# UFl_calKit.net
KiCad netlist of a schematic drawn in Altium Designer
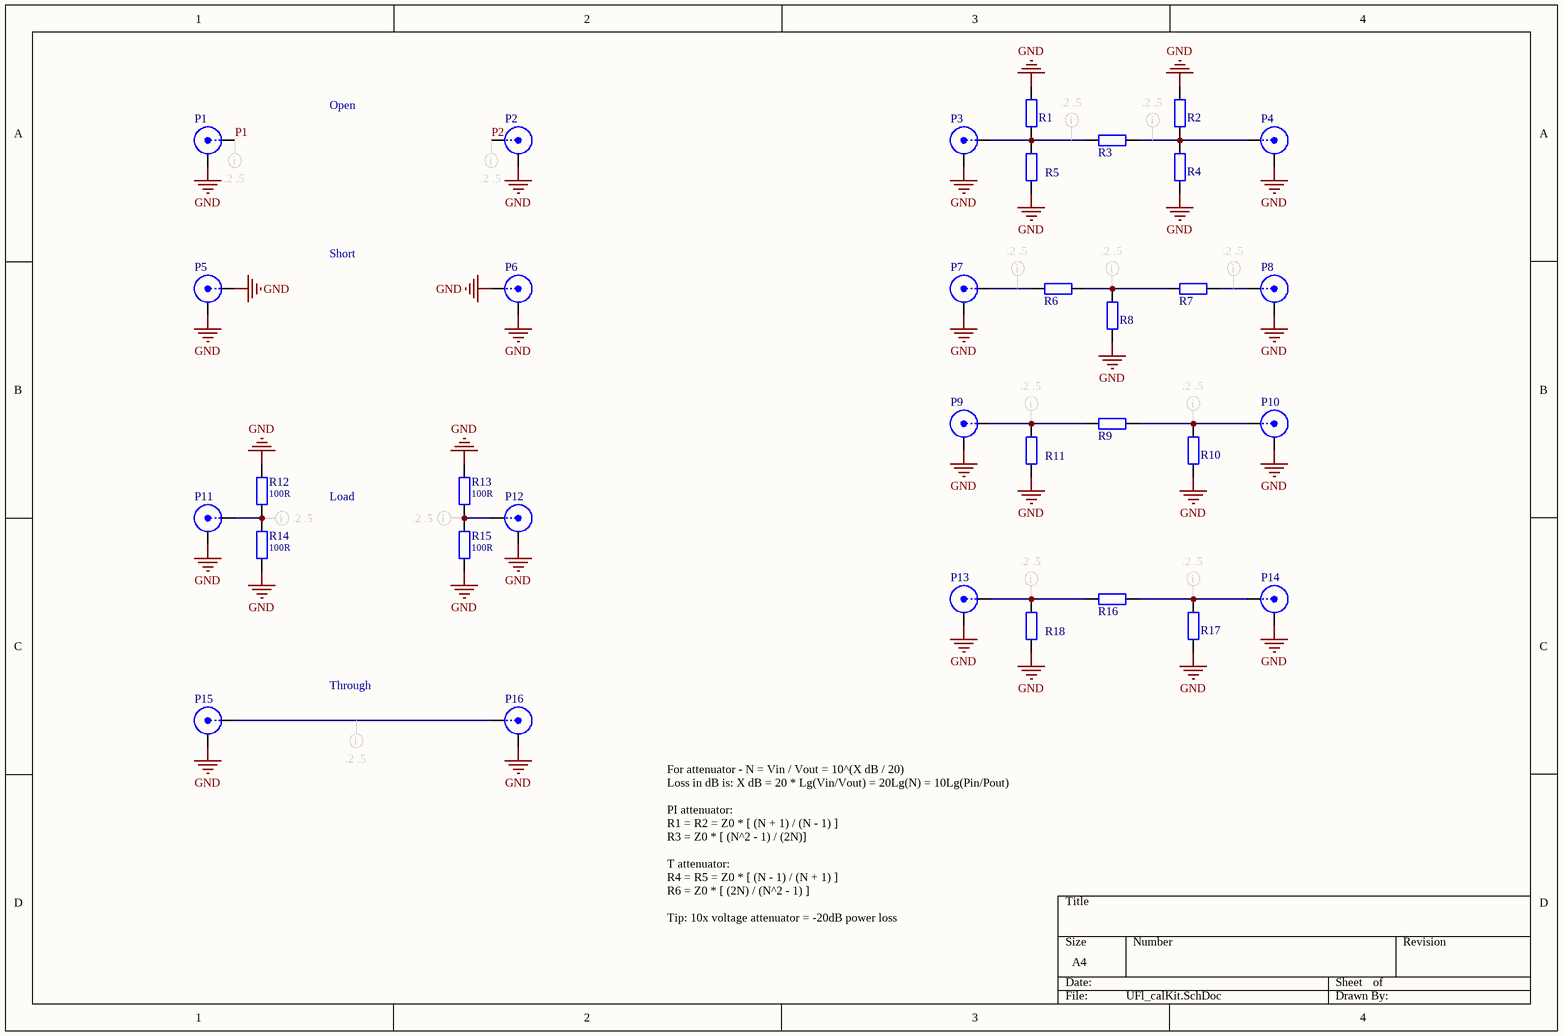
[diagram p0: UFl_calKit.SchDoc]

(export (version "E")
  (design (tool "Eeschema 10.0.6"))
  (components
    (comp (ref "P1")
      (value "U.Fl.")
      (footprint "U.FL CalKit")
      (libsource (lib "Miscellaneous Connectors") (part "BNC"))
    )
    (comp (ref "P2")
      (value "U.Fl.")
      (footprint "U.FL CalKit")
      (libsource (lib "Miscellaneous Connectors") (part "BNC"))
    )
    (comp (ref "P3")
      (value "U.Fl.")
      (footprint "U.FL CalKit")
      (libsource (lib "Miscellaneous Connectors") (part "BNC"))
    )
    (comp (ref "P4")
      (value "U.Fl.")
      (footprint "U.FL CalKit")
      (libsource (lib "Miscellaneous Connectors") (part "BNC"))
    )
    (comp (ref "P5")
      (value "U.Fl.")
      (footprint "U.FL-R-SMT-1(10)")
      (libsource (lib "Miscellaneous Connectors") (part "BNC"))
    )
    (comp (ref "P6")
      (value "U.Fl.")
      (footprint "U.FL-R-SMT-1(10)")
      (libsource (lib "Miscellaneous Connectors") (part "BNC"))
    )
    (comp (ref "P7")
      (value "U.Fl.")
      (footprint "U.FL CalKit")
      (libsource (lib "Miscellaneous Connectors") (part "BNC"))
    )
    (comp (ref "P8")
      (value "U.Fl.")
      (footprint "U.FL CalKit")
      (libsource (lib "Miscellaneous Connectors") (part "BNC"))
    )
    (comp (ref "P9")
      (value "U.Fl.")
      (footprint "U.FL CalKit")
      (libsource (lib "Miscellaneous Connectors") (part "BNC"))
    )
    (comp (ref "P10")
      (value "U.Fl.")
      (footprint "U.FL CalKit")
      (libsource (lib "Miscellaneous Connectors") (part "BNC"))
    )
    (comp (ref "P11")
      (value "U.Fl.")
      (footprint "U.FL CalKit")
      (libsource (lib "Miscellaneous Connectors") (part "BNC"))
    )
    (comp (ref "P12")
      (value "U.Fl.")
      (footprint "U.FL CalKit")
      (libsource (lib "Miscellaneous Connectors") (part "BNC"))
    )
    (comp (ref "P13")
      (value "U.Fl.")
      (footprint "U.FL CalKit")
      (libsource (lib "Miscellaneous Connectors") (part "BNC"))
    )
    (comp (ref "P14")
      (value "U.Fl.")
      (footprint "U.FL CalKit")
      (libsource (lib "Miscellaneous Connectors") (part "BNC"))
    )
    (comp (ref "P15")
      (value "U.Fl.")
      (footprint "U.FL CalKit")
      (libsource (lib "Miscellaneous Connectors") (part "BNC"))
    )
    (comp (ref "P16")
      (value "U.Fl.")
      (footprint "U.FL CalKit")
      (libsource (lib "Miscellaneous Connectors") (part "BNC"))
    )
    (comp (ref "R1")
      (value "0R, 50 V, 0402, 62.5 mW, ± 1%")
      (footprint "C SMD ceramic 0402 RF with silkscreen")
      (fields (field (name "PART NUMBER") "0402WGJ0000TCE") (field (name "MANUFACTURER") "ROYAL OHM"))
      (libsource (lib "Resistors") (part "Resistor"))
    )
    (comp (ref "R2")
      (value "0R, 50 V, 0402, 62.5 mW, ± 1%")
      (footprint "C SMD ceramic 0402 RF with silkscreen")
      (fields (field (name "PART NUMBER") "0402WGJ0000TCE") (field (name "MANUFACTURER") "ROYAL OHM"))
      (libsource (lib "Resistors") (part "Resistor"))
    )
    (comp (ref "R3")
      (value "0R, 50 V, 0402, 62.5 mW, ± 1%")
      (footprint "C SMD ceramic 0402 RF with silkscreen")
      (fields (field (name "PART NUMBER") "0402WGJ0000TCE") (field (name "MANUFACTURER") "ROYAL OHM"))
      (libsource (lib "Resistors") (part "Resistor"))
    )
    (comp (ref "R4")
      (value "0R, 50 V, 0402, 62.5 mW, ± 1%")
      (footprint "C SMD ceramic 0402 RF with silkscreen")
      (fields (field (name "PART NUMBER") "0402WGJ0000TCE") (field (name "MANUFACTURER") "ROYAL OHM"))
      (libsource (lib "Resistors") (part "Resistor"))
    )
    (comp (ref "R5")
      (value "0R, 50 V, 0402, 62.5 mW, ± 1%")
      (footprint "C SMD ceramic 0402 RF with silkscreen")
      (fields (field (name "PART NUMBER") "0402WGJ0000TCE") (field (name "MANUFACTURER") "ROYAL OHM"))
      (libsource (lib "Resistors") (part "Resistor"))
    )
    (comp (ref "R6")
      (value "0R, 50 V, 0402, 62.5 mW, ± 1%")
      (footprint "WE Match B")
      (fields (field (name "PART NUMBER") "0402WGJ0000TCE") (field (name "MANUFACTURER") "ROYAL OHM"))
      (libsource (lib "Resistors") (part "Resistor"))
    )
    (comp (ref "R7")
      (value "0R, 50 V, 0402, 62.5 mW, ± 1%")
      (footprint "WE Match B")
      (fields (field (name "PART NUMBER") "0402WGJ0000TCE") (field (name "MANUFACTURER") "ROYAL OHM"))
      (libsource (lib "Resistors") (part "Resistor"))
    )
    (comp (ref "R8")
      (value "0R, 50 V, 0402, 62.5 mW, ± 1%")
      (footprint "WE Match B")
      (fields (field (name "PART NUMBER") "0402WGJ0000TCE") (field (name "MANUFACTURER") "ROYAL OHM"))
      (libsource (lib "Resistors") (part "Resistor"))
    )
    (comp (ref "R9")
      (value "0R, 50 V, 0402, 62.5 mW, ± 1%")
      (footprint "WE Match B")
      (fields (field (name "PART NUMBER") "0402WGJ0000TCE") (field (name "MANUFACTURER") "ROYAL OHM"))
      (libsource (lib "Resistors") (part "Resistor"))
    )
    (comp (ref "R10")
      (value "0R, 50 V, 0402, 62.5 mW, ± 1%")
      (footprint "WE Match B")
      (fields (field (name "PART NUMBER") "0402WGJ0000TCE") (field (name "MANUFACTURER") "ROYAL OHM"))
      (libsource (lib "Resistors") (part "Resistor"))
    )
    (comp (ref "R11")
      (value "0R, 50 V, 0402, 62.5 mW, ± 1%")
      (footprint "WE Match B")
      (fields (field (name "PART NUMBER") "0402WGJ0000TCE") (field (name "MANUFACTURER") "ROYAL OHM"))
      (libsource (lib "Resistors") (part "Resistor"))
    )
    (comp (ref "R12")
      (value "100R")
      (footprint "C SMD ceramic 0402 RF")
      (description "100R, 50 V, 0402, 62.5 mW, ± 1%")
      (fields (field (name "PART NUMBER") "AC0402FR-10100RL") (field (name "MANUFACTURER") "YAGEO"))
      (libsource (lib "Resistors") (part "Resistor"))
    )
    (comp (ref "R13")
      (value "100R")
      (footprint "C SMD ceramic 0402 RF")
      (description "100R, 50 V, 0402, 62.5 mW, ± 1%")
      (fields (field (name "PART NUMBER") "AC0402FR-10100RL") (field (name "MANUFACTURER") "YAGEO"))
      (libsource (lib "Resistors") (part "Resistor"))
    )
    (comp (ref "R14")
      (value "100R")
      (footprint "C SMD ceramic 0402 RF")
      (description "100R, 50 V, 0402, 62.5 mW, ± 1%")
      (fields (field (name "PART NUMBER") "AC0402FR-10100RL") (field (name "MANUFACTURER") "YAGEO"))
      (libsource (lib "Resistors") (part "Resistor"))
    )
    (comp (ref "R15")
      (value "100R")
      (footprint "C SMD ceramic 0402 RF")
      (description "100R, 50 V, 0402, 62.5 mW, ± 1%")
      (fields (field (name "PART NUMBER") "AC0402FR-10100RL") (field (name "MANUFACTURER") "YAGEO"))
      (libsource (lib "Resistors") (part "Resistor"))
    )
    (comp (ref "R16")
      (value "0R, 50 V, 0402, 62.5 mW, ± 1%")
      (footprint "WE Match B")
      (fields (field (name "PART NUMBER") "0402WGJ0000TCE") (field (name "MANUFACTURER") "ROYAL OHM"))
      (libsource (lib "Resistors") (part "Resistor"))
    )
    (comp (ref "R17")
      (value "0R, 50 V, 0402, 62.5 mW, ± 1%")
      (footprint "WE Match B")
      (fields (field (name "PART NUMBER") "0402WGJ0000TCE") (field (name "MANUFACTURER") "ROYAL OHM"))
      (libsource (lib "Resistors") (part "Resistor"))
    )
    (comp (ref "R18")
      (value "0R, 50 V, 0402, 62.5 mW, ± 1%")
      (footprint "WE Match B")
      (fields (field (name "PART NUMBER") "0402WGJ0000TCE") (field (name "MANUFACTURER") "ROYAL OHM"))
      (libsource (lib "Resistors") (part "Resistor"))
    )
  )
  (nets
    (net (code "1") (name "/P1") (class "Default")
      (node (ref "P1") (pin "1") (pinfunction "X_1") (pintype "passive"))
    )
    (net (code "2") (name "/P2") (class "Default")
      (node (ref "P2") (pin "1") (pinfunction "X_1") (pintype "passive"))
    )
    (net (code "3") (name "GND") (class "Default")
      (node (ref "P1") (pin "2") (pinfunction "Y_2") (pintype "passive"))
      (node (ref "P10") (pin "2") (pinfunction "Y_2") (pintype "passive"))
      (node (ref "P11") (pin "2") (pinfunction "Y_2") (pintype "passive"))
      (node (ref "P12") (pin "2") (pinfunction "Y_2") (pintype "passive"))
      (node (ref "P13") (pin "2") (pinfunction "Y_2") (pintype "passive"))
      (node (ref "P14") (pin "2") (pinfunction "Y_2") (pintype "passive"))
      (node (ref "P15") (pin "2") (pinfunction "Y_2") (pintype "passive"))
      (node (ref "P16") (pin "2") (pinfunction "Y_2") (pintype "passive"))
      (node (ref "P2") (pin "2") (pinfunction "Y_2") (pintype "passive"))
      (node (ref "P3") (pin "2") (pinfunction "Y_2") (pintype "passive"))
      (node (ref "P4") (pin "2") (pinfunction "Y_2") (pintype "passive"))
      (node (ref "P5") (pin "1") (pinfunction "X_1") (pintype "passive"))
      (node (ref "P5") (pin "2") (pinfunction "Y_2") (pintype "passive"))
      (node (ref "P6") (pin "1") (pinfunction "X_1") (pintype "passive"))
      (node (ref "P6") (pin "2") (pinfunction "Y_2") (pintype "passive"))
      (node (ref "P7") (pin "2") (pinfunction "Y_2") (pintype "passive"))
      (node (ref "P8") (pin "2") (pinfunction "Y_2") (pintype "passive"))
      (node (ref "P9") (pin "2") (pinfunction "Y_2") (pintype "passive"))
      (node (ref "R1") (pin "2") (pinfunction "2_2") (pintype "passive"))
      (node (ref "R10") (pin "2") (pinfunction "2_2") (pintype "passive"))
      (node (ref "R11") (pin "2") (pinfunction "2_2") (pintype "passive"))
      (node (ref "R12") (pin "1") (pinfunction "1_1") (pintype "passive"))
      (node (ref "R13") (pin "1") (pinfunction "1_1") (pintype "passive"))
      (node (ref "R14") (pin "1") (pinfunction "1_1") (pintype "passive"))
      (node (ref "R15") (pin "1") (pinfunction "1_1") (pintype "passive"))
      (node (ref "R17") (pin "2") (pinfunction "2_2") (pintype "passive"))
      (node (ref "R18") (pin "2") (pinfunction "2_2") (pintype "passive"))
      (node (ref "R2") (pin "2") (pinfunction "2_2") (pintype "passive"))
      (node (ref "R4") (pin "2") (pinfunction "2_2") (pintype "passive"))
      (node (ref "R5") (pin "2") (pinfunction "2_2") (pintype "passive"))
      (node (ref "R8") (pin "2") (pinfunction "2_2") (pintype "passive"))
    )
    (net (code "4") (name "Net-(P3-X)") (class "Default")
      (node (ref "P3") (pin "1") (pinfunction "X_1") (pintype "passive"))
      (node (ref "R1") (pin "1") (pinfunction "1_1") (pintype "passive"))
      (node (ref "R3") (pin "2") (pinfunction "2_2") (pintype "passive"))
      (node (ref "R5") (pin "1") (pinfunction "1_1") (pintype "passive"))
    )
    (net (code "5") (name "Net-(P4-X)") (class "Default")
      (node (ref "P4") (pin "1") (pinfunction "X_1") (pintype "passive"))
      (node (ref "R2") (pin "1") (pinfunction "1_1") (pintype "passive"))
      (node (ref "R3") (pin "1") (pinfunction "1_1") (pintype "passive"))
      (node (ref "R4") (pin "1") (pinfunction "1_1") (pintype "passive"))
    )
    (net (code "6") (name "Net-(P7-X)") (class "Default")
      (node (ref "P7") (pin "1") (pinfunction "X_1") (pintype "passive"))
      (node (ref "R6") (pin "1") (pinfunction "1_1") (pintype "passive"))
    )
    (net (code "7") (name "Net-(P8-X)") (class "Default")
      (node (ref "P8") (pin "1") (pinfunction "X_1") (pintype "passive"))
      (node (ref "R7") (pin "2") (pinfunction "2_2") (pintype "passive"))
    )
    (net (code "8") (name "Net-(P9-X)") (class "Default")
      (node (ref "P9") (pin "1") (pinfunction "X_1") (pintype "passive"))
      (node (ref "R11") (pin "1") (pinfunction "1_1") (pintype "passive"))
      (node (ref "R9") (pin "2") (pinfunction "2_2") (pintype "passive"))
    )
    (net (code "9") (name "Net-(P10-X)") (class "Default")
      (node (ref "P10") (pin "1") (pinfunction "X_1") (pintype "passive"))
      (node (ref "R10") (pin "1") (pinfunction "1_1") (pintype "passive"))
      (node (ref "R9") (pin "1") (pinfunction "1_1") (pintype "passive"))
    )
    (net (code "10") (name "Net-(P11-X)") (class "Default")
      (node (ref "P11") (pin "1") (pinfunction "X_1") (pintype "passive"))
      (node (ref "R12") (pin "2") (pinfunction "2_2") (pintype "passive"))
      (node (ref "R14") (pin "2") (pinfunction "2_2") (pintype "passive"))
    )
    (net (code "11") (name "Net-(P12-X)") (class "Default")
      (node (ref "P12") (pin "1") (pinfunction "X_1") (pintype "passive"))
      (node (ref "R13") (pin "2") (pinfunction "2_2") (pintype "passive"))
      (node (ref "R15") (pin "2") (pinfunction "2_2") (pintype "passive"))
    )
    (net (code "12") (name "Net-(P13-X)") (class "Default")
      (node (ref "P13") (pin "1") (pinfunction "X_1") (pintype "passive"))
      (node (ref "R16") (pin "2") (pinfunction "2_2") (pintype "passive"))
      (node (ref "R18") (pin "1") (pinfunction "1_1") (pintype "passive"))
    )
    (net (code "13") (name "Net-(P14-X)") (class "Default")
      (node (ref "P14") (pin "1") (pinfunction "X_1") (pintype "passive"))
      (node (ref "R16") (pin "1") (pinfunction "1_1") (pintype "passive"))
      (node (ref "R17") (pin "1") (pinfunction "1_1") (pintype "passive"))
    )
    (net (code "14") (name "Net-(P15-X)") (class "Default")
      (node (ref "P15") (pin "1") (pinfunction "X_1") (pintype "passive"))
      (node (ref "P16") (pin "1") (pinfunction "X_1") (pintype "passive"))
    )
    (net (code "15") (name "Net-(R6-Pad2)") (class "Default")
      (node (ref "R6") (pin "2") (pinfunction "2_2") (pintype "passive"))
      (node (ref "R7") (pin "1") (pinfunction "1_1") (pintype "passive"))
      (node (ref "R8") (pin "1") (pinfunction "1_1") (pintype "passive"))
    )
  )
)
